# CONTROLS.net
KiCad netlist of a schematic drawn in Altium Designer
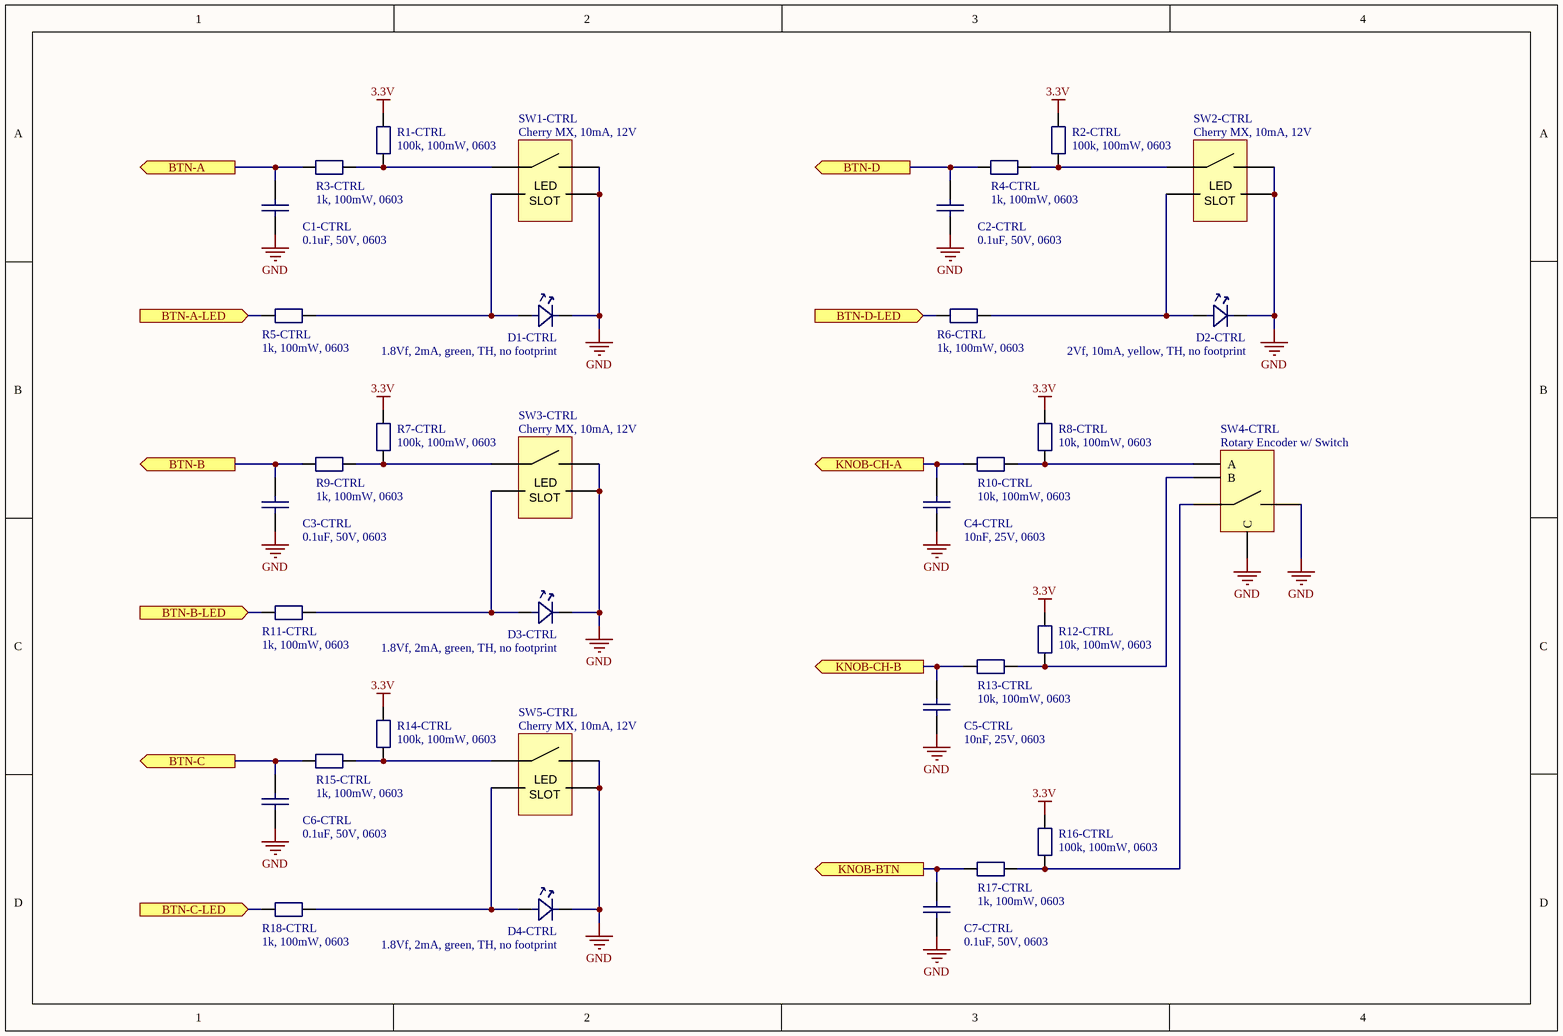
[diagram p0: CONTROLS.SchDoc]

(export (version "E")
  (design (tool "Eeschema 10.0.6"))
  (components
    (comp (ref "C1-CTRL")
      (value "0.1uF, 50V, 0603")
      (footprint "0603 [1608]")
      (fields (field (name "MANUFACTURER") "MULTICOMP PRO"))
      (libsource (lib "SCH-LIB") (part "Capacitor"))
    )
    (comp (ref "C2-CTRL")
      (value "0.1uF, 50V, 0603")
      (footprint "0603 [1608]")
      (fields (field (name "MANUFACTURER") "MULTICOMP PRO"))
      (libsource (lib "SCH-LIB") (part "Capacitor"))
    )
    (comp (ref "C3-CTRL")
      (value "0.1uF, 50V, 0603")
      (footprint "0603 [1608]")
      (fields (field (name "MANUFACTURER") "MULTICOMP PRO"))
      (libsource (lib "SCH-LIB") (part "Capacitor"))
    )
    (comp (ref "C4-CTRL")
      (value "10nF, 25V, 0603")
      (footprint "0603 [1608]")
      (fields (field (name "MANUFACTURER") "YAGEO"))
      (libsource (lib "SCH-LIB") (part "Capacitor"))
    )
    (comp (ref "C5-CTRL")
      (value "10nF, 25V, 0603")
      (footprint "0603 [1608]")
      (fields (field (name "MANUFACTURER") "YAGEO"))
      (libsource (lib "SCH-LIB") (part "Capacitor"))
    )
    (comp (ref "C6-CTRL")
      (value "0.1uF, 50V, 0603")
      (footprint "0603 [1608]")
      (fields (field (name "MANUFACTURER") "MULTICOMP PRO"))
      (libsource (lib "SCH-LIB") (part "Capacitor"))
    )
    (comp (ref "C7-CTRL")
      (value "0.1uF, 50V, 0603")
      (footprint "0603 [1608]")
      (fields (field (name "MANUFACTURER") "MULTICOMP PRO"))
      (libsource (lib "SCH-LIB") (part "Capacitor"))
    )
    (comp (ref "D1-CTRL")
      (value "1.8Vf, 2mA, green, TH, no footprint")
      (footprint "LED 0603 [1608]")
      (fields (field (name "MANUFACTURER") "MULTICOMP PRO"))
      (libsource (lib "SCH-LIB") (part "LED"))
    )
    (comp (ref "D2-CTRL")
      (value "2Vf, 10mA, yellow, TH, no footprint")
      (footprint "LED 0603 [1608]")
      (fields (field (name "MANUFACTURER") "BROADCOM"))
      (libsource (lib "SCH-LIB") (part "LED"))
    )
    (comp (ref "D3-CTRL")
      (value "1.8Vf, 2mA, green, TH, no footprint")
      (footprint "LED 0603 [1608]")
      (fields (field (name "MANUFACTURER") "MULTICOMP PRO"))
      (libsource (lib "SCH-LIB") (part "LED"))
    )
    (comp (ref "D4-CTRL")
      (value "1.8Vf, 2mA, green, TH, no footprint")
      (footprint "LED 0603 [1608]")
      (fields (field (name "MANUFACTURER") "MULTICOMP PRO"))
      (libsource (lib "SCH-LIB") (part "LED"))
    )
    (comp (ref "R1-CTRL")
      (value "100k, 100mW, 0603")
      (footprint "0603 [1608]")
      (fields (field (name "MANUFACTURER") "YAGEO"))
      (libsource (lib "SCH-LIB") (part "Resistor"))
    )
    (comp (ref "R2-CTRL")
      (value "100k, 100mW, 0603")
      (footprint "0603 [1608]")
      (fields (field (name "MANUFACTURER") "YAGEO"))
      (libsource (lib "SCH-LIB") (part "Resistor"))
    )
    (comp (ref "R3-CTRL")
      (value "1k, 100mW, 0603")
      (footprint "0603 [1608]")
      (fields (field (name "MANUFACTURER") "BOURNS"))
      (libsource (lib "SCH-LIB") (part "Resistor"))
    )
    (comp (ref "R4-CTRL")
      (value "1k, 100mW, 0603")
      (footprint "0603 [1608]")
      (fields (field (name "MANUFACTURER") "BOURNS"))
      (libsource (lib "SCH-LIB") (part "Resistor"))
    )
    (comp (ref "R5-CTRL")
      (value "1k, 100mW, 0603")
      (footprint "0603 [1608]")
      (fields (field (name "MANUFACTURER") "BOURNS"))
      (libsource (lib "SCH-LIB") (part "Resistor"))
    )
    (comp (ref "R6-CTRL")
      (value "1k, 100mW, 0603")
      (footprint "0603 [1608]")
      (fields (field (name "MANUFACTURER") "BOURNS"))
      (libsource (lib "SCH-LIB") (part "Resistor"))
    )
    (comp (ref "R7-CTRL")
      (value "100k, 100mW, 0603")
      (footprint "0603 [1608]")
      (fields (field (name "MANUFACTURER") "YAGEO"))
      (libsource (lib "SCH-LIB") (part "Resistor"))
    )
    (comp (ref "R8-CTRL")
      (value "10k, 100mW, 0603")
      (footprint "0603 [1608]")
      (fields (field (name "MANUFACTURER") "YAGEO"))
      (libsource (lib "SCH-LIB") (part "Resistor"))
    )
    (comp (ref "R9-CTRL")
      (value "1k, 100mW, 0603")
      (footprint "0603 [1608]")
      (fields (field (name "MANUFACTURER") "BOURNS"))
      (libsource (lib "SCH-LIB") (part "Resistor"))
    )
    (comp (ref "R10-CTRL")
      (value "10k, 100mW, 0603")
      (footprint "0603 [1608]")
      (fields (field (name "MANUFACTURER") "YAGEO"))
      (libsource (lib "SCH-LIB") (part "Resistor"))
    )
    (comp (ref "R11-CTRL")
      (value "1k, 100mW, 0603")
      (footprint "0603 [1608]")
      (fields (field (name "MANUFACTURER") "BOURNS"))
      (libsource (lib "SCH-LIB") (part "Resistor"))
    )
    (comp (ref "R12-CTRL")
      (value "10k, 100mW, 0603")
      (footprint "0603 [1608]")
      (fields (field (name "MANUFACTURER") "YAGEO"))
      (libsource (lib "SCH-LIB") (part "Resistor"))
    )
    (comp (ref "R13-CTRL")
      (value "10k, 100mW, 0603")
      (footprint "0603 [1608]")
      (fields (field (name "MANUFACTURER") "YAGEO"))
      (libsource (lib "SCH-LIB") (part "Resistor"))
    )
    (comp (ref "R14-CTRL")
      (value "100k, 100mW, 0603")
      (footprint "0603 [1608]")
      (fields (field (name "MANUFACTURER") "YAGEO"))
      (libsource (lib "SCH-LIB") (part "Resistor"))
    )
    (comp (ref "R15-CTRL")
      (value "1k, 100mW, 0603")
      (footprint "0603 [1608]")
      (fields (field (name "MANUFACTURER") "BOURNS"))
      (libsource (lib "SCH-LIB") (part "Resistor"))
    )
    (comp (ref "R16-CTRL")
      (value "100k, 100mW, 0603")
      (footprint "0603 [1608]")
      (fields (field (name "MANUFACTURER") "YAGEO"))
      (libsource (lib "SCH-LIB") (part "Resistor"))
    )
    (comp (ref "R17-CTRL")
      (value "1k, 100mW, 0603")
      (footprint "0603 [1608]")
      (fields (field (name "MANUFACTURER") "BOURNS"))
      (libsource (lib "SCH-LIB") (part "Resistor"))
    )
    (comp (ref "R18-CTRL")
      (value "1k, 100mW, 0603")
      (footprint "0603 [1608]")
      (fields (field (name "MANUFACTURER") "BOURNS"))
      (libsource (lib "SCH-LIB") (part "Resistor"))
    )
    (comp (ref "SW1-CTRL")
      (value "Cherry MX, 10mA, 12V")
      (footprint "Cherry MX Switch")
      (fields (field (name "MANUFACTURER") "Cherry Americas LLC"))
      (libsource (lib "SCH-LIB") (part "Cherry MX Switch"))
    )
    (comp (ref "SW2-CTRL")
      (value "Cherry MX, 10mA, 12V")
      (footprint "Cherry MX Switch")
      (fields (field (name "MANUFACTURER") "Cherry Americas LLC"))
      (libsource (lib "SCH-LIB") (part "Cherry MX Switch"))
    )
    (comp (ref "SW3-CTRL")
      (value "Cherry MX, 10mA, 12V")
      (footprint "Cherry MX Switch")
      (fields (field (name "MANUFACTURER") "Cherry Americas LLC"))
      (libsource (lib "SCH-LIB") (part "Cherry MX Switch"))
    )
    (comp (ref "SW4-CTRL")
      (value "Rotary Encoder w/ Switch")
      (footprint "Rotary Encoder w/ Switch (Bourns)")
      (fields (field (name "MANUFACTURER") "Bourns"))
      (libsource (lib "SCH-LIB") (part "Rotary Encoder w/ Switch"))
    )
    (comp (ref "SW5-CTRL")
      (value "Cherry MX, 10mA, 12V")
      (footprint "Cherry MX Switch")
      (fields (field (name "MANUFACTURER") "Cherry Americas LLC"))
      (libsource (lib "SCH-LIB") (part "Cherry MX Switch"))
    )
  )
  (nets
    (net (code "1") (name "/BTN-A") (class "Default")
      (node (ref "C1-CTRL") (pin "2") (pinfunction "2_2") (pintype "passive"))
      (node (ref "R3-CTRL") (pin "2") (pinfunction "2_2") (pintype "passive"))
    )
    (net (code "2") (name "/BTN-A-LED") (class "Default")
      (node (ref "R5-CTRL") (pin "1") (pinfunction "1_1") (pintype "passive"))
    )
    (net (code "3") (name "/BTN-B") (class "Default")
      (node (ref "C3-CTRL") (pin "2") (pinfunction "2_2") (pintype "passive"))
      (node (ref "R9-CTRL") (pin "2") (pinfunction "2_2") (pintype "passive"))
    )
    (net (code "4") (name "/BTN-B-LED") (class "Default")
      (node (ref "R11-CTRL") (pin "1") (pinfunction "1_1") (pintype "passive"))
    )
    (net (code "5") (name "/BTN-C") (class "Default")
      (node (ref "C6-CTRL") (pin "2") (pinfunction "2_2") (pintype "passive"))
      (node (ref "R15-CTRL") (pin "2") (pinfunction "2_2") (pintype "passive"))
    )
    (net (code "6") (name "/BTN-C-LED") (class "Default")
      (node (ref "R18-CTRL") (pin "1") (pinfunction "1_1") (pintype "passive"))
    )
    (net (code "7") (name "/BTN-D") (class "Default")
      (node (ref "C2-CTRL") (pin "2") (pinfunction "2_2") (pintype "passive"))
      (node (ref "R4-CTRL") (pin "2") (pinfunction "2_2") (pintype "passive"))
    )
    (net (code "8") (name "/BTN-D-LED") (class "Default")
      (node (ref "R6-CTRL") (pin "1") (pinfunction "1_1") (pintype "passive"))
    )
    (net (code "9") (name "/KNOB-BTN") (class "Default")
      (node (ref "C7-CTRL") (pin "2") (pinfunction "2_2") (pintype "passive"))
      (node (ref "R17-CTRL") (pin "2") (pinfunction "2_2") (pintype "passive"))
    )
    (net (code "10") (name "/KNOB-CH-A") (class "Default")
      (node (ref "C4-CTRL") (pin "2") (pinfunction "2_2") (pintype "passive"))
      (node (ref "R10-CTRL") (pin "2") (pinfunction "2_2") (pintype "passive"))
    )
    (net (code "11") (name "/KNOB-CH-B") (class "Default")
      (node (ref "C5-CTRL") (pin "2") (pinfunction "2_2") (pintype "passive"))
      (node (ref "R13-CTRL") (pin "2") (pinfunction "2_2") (pintype "passive"))
    )
    (net (code "12") (name "3.3V") (class "Default")
      (node (ref "R1-CTRL") (pin "2") (pinfunction "2_2") (pintype "passive"))
      (node (ref "R12-CTRL") (pin "2") (pinfunction "2_2") (pintype "passive"))
      (node (ref "R14-CTRL") (pin "2") (pinfunction "2_2") (pintype "passive"))
      (node (ref "R16-CTRL") (pin "2") (pinfunction "2_2") (pintype "passive"))
      (node (ref "R2-CTRL") (pin "2") (pinfunction "2_2") (pintype "passive"))
      (node (ref "R7-CTRL") (pin "2") (pinfunction "2_2") (pintype "passive"))
      (node (ref "R8-CTRL") (pin "2") (pinfunction "2_2") (pintype "passive"))
    )
    (net (code "13") (name "GND") (class "Default")
      (node (ref "C1-CTRL") (pin "1") (pinfunction "1_1") (pintype "passive"))
      (node (ref "C2-CTRL") (pin "1") (pinfunction "1_1") (pintype "passive"))
      (node (ref "C3-CTRL") (pin "1") (pinfunction "1_1") (pintype "passive"))
      (node (ref "C4-CTRL") (pin "1") (pinfunction "1_1") (pintype "passive"))
      (node (ref "C5-CTRL") (pin "1") (pinfunction "1_1") (pintype "passive"))
      (node (ref "C6-CTRL") (pin "1") (pinfunction "1_1") (pintype "passive"))
      (node (ref "C7-CTRL") (pin "1") (pinfunction "1_1") (pintype "passive"))
      (node (ref "D1-CTRL") (pin "1") (pinfunction "1_1") (pintype "passive"))
      (node (ref "D2-CTRL") (pin "1") (pinfunction "1_1") (pintype "passive"))
      (node (ref "D3-CTRL") (pin "1") (pinfunction "1_1") (pintype "passive"))
      (node (ref "D4-CTRL") (pin "1") (pinfunction "1_1") (pintype "passive"))
      (node (ref "SW1-CTRL") (pin "2") (pinfunction "2_2") (pintype "passive"))
      (node (ref "SW1-CTRL") (pin "4") (pinfunction "4_4") (pintype "passive"))
      (node (ref "SW2-CTRL") (pin "2") (pinfunction "2_2") (pintype "passive"))
      (node (ref "SW2-CTRL") (pin "4") (pinfunction "4_4") (pintype "passive"))
      (node (ref "SW3-CTRL") (pin "2") (pinfunction "2_2") (pintype "passive"))
      (node (ref "SW3-CTRL") (pin "4") (pinfunction "4_4") (pintype "passive"))
      (node (ref "SW4-CTRL") (pin "2") (pinfunction "2_2") (pintype "passive"))
      (node (ref "SW4-CTRL") (pin "C") (pinfunction "C_C") (pintype "passive"))
      (node (ref "SW5-CTRL") (pin "2") (pinfunction "2_2") (pintype "passive"))
      (node (ref "SW5-CTRL") (pin "4") (pinfunction "4_4") (pintype "passive"))
    )
    (net (code "14") (name "Net-(D1-CTRL-Pad2)") (class "Default")
      (node (ref "D1-CTRL") (pin "2") (pinfunction "2_2") (pintype "passive"))
      (node (ref "R5-CTRL") (pin "2") (pinfunction "2_2") (pintype "passive"))
      (node (ref "SW1-CTRL") (pin "3") (pinfunction "3_3") (pintype "passive"))
    )
    (net (code "15") (name "Net-(D2-CTRL-Pad2)") (class "Default")
      (node (ref "D2-CTRL") (pin "2") (pinfunction "2_2") (pintype "passive"))
      (node (ref "R6-CTRL") (pin "2") (pinfunction "2_2") (pintype "passive"))
      (node (ref "SW2-CTRL") (pin "3") (pinfunction "3_3") (pintype "passive"))
    )
    (net (code "16") (name "Net-(D3-CTRL-Pad2)") (class "Default")
      (node (ref "D3-CTRL") (pin "2") (pinfunction "2_2") (pintype "passive"))
      (node (ref "R11-CTRL") (pin "2") (pinfunction "2_2") (pintype "passive"))
      (node (ref "SW3-CTRL") (pin "3") (pinfunction "3_3") (pintype "passive"))
    )
    (net (code "17") (name "Net-(D4-CTRL-Pad2)") (class "Default")
      (node (ref "D4-CTRL") (pin "2") (pinfunction "2_2") (pintype "passive"))
      (node (ref "R18-CTRL") (pin "2") (pinfunction "2_2") (pintype "passive"))
      (node (ref "SW5-CTRL") (pin "3") (pinfunction "3_3") (pintype "passive"))
    )
    (net (code "18") (name "Net-(R1-CTRL-Pad1)") (class "Default")
      (node (ref "R1-CTRL") (pin "1") (pinfunction "1_1") (pintype "passive"))
      (node (ref "R3-CTRL") (pin "1") (pinfunction "1_1") (pintype "passive"))
      (node (ref "SW1-CTRL") (pin "1") (pinfunction "1_1") (pintype "passive"))
    )
    (net (code "19") (name "Net-(R2-CTRL-Pad1)") (class "Default")
      (node (ref "R2-CTRL") (pin "1") (pinfunction "1_1") (pintype "passive"))
      (node (ref "R4-CTRL") (pin "1") (pinfunction "1_1") (pintype "passive"))
      (node (ref "SW2-CTRL") (pin "1") (pinfunction "1_1") (pintype "passive"))
    )
    (net (code "20") (name "Net-(R7-CTRL-Pad1)") (class "Default")
      (node (ref "R7-CTRL") (pin "1") (pinfunction "1_1") (pintype "passive"))
      (node (ref "R9-CTRL") (pin "1") (pinfunction "1_1") (pintype "passive"))
      (node (ref "SW3-CTRL") (pin "1") (pinfunction "1_1") (pintype "passive"))
    )
    (net (code "21") (name "Net-(R10-CTRL-Pad1)") (class "Default")
      (node (ref "R10-CTRL") (pin "1") (pinfunction "1_1") (pintype "passive"))
      (node (ref "R8-CTRL") (pin "1") (pinfunction "1_1") (pintype "passive"))
      (node (ref "SW4-CTRL") (pin "A") (pinfunction "A_A") (pintype "passive"))
    )
    (net (code "22") (name "Net-(R12-CTRL-Pad1)") (class "Default")
      (node (ref "R12-CTRL") (pin "1") (pinfunction "1_1") (pintype "passive"))
      (node (ref "R13-CTRL") (pin "1") (pinfunction "1_1") (pintype "passive"))
      (node (ref "SW4-CTRL") (pin "B") (pinfunction "B_B") (pintype "passive"))
    )
    (net (code "23") (name "Net-(R14-CTRL-Pad1)") (class "Default")
      (node (ref "R14-CTRL") (pin "1") (pinfunction "1_1") (pintype "passive"))
      (node (ref "R15-CTRL") (pin "1") (pinfunction "1_1") (pintype "passive"))
      (node (ref "SW5-CTRL") (pin "1") (pinfunction "1_1") (pintype "passive"))
    )
    (net (code "24") (name "Net-(R16-CTRL-Pad1)") (class "Default")
      (node (ref "R16-CTRL") (pin "1") (pinfunction "1_1") (pintype "passive"))
      (node (ref "R17-CTRL") (pin "1") (pinfunction "1_1") (pintype "passive"))
      (node (ref "SW4-CTRL") (pin "1") (pinfunction "1_1") (pintype "passive"))
    )
  )
)
